# 02_-_MCU.net
KiCad netlist of a schematic drawn in Altium Designer
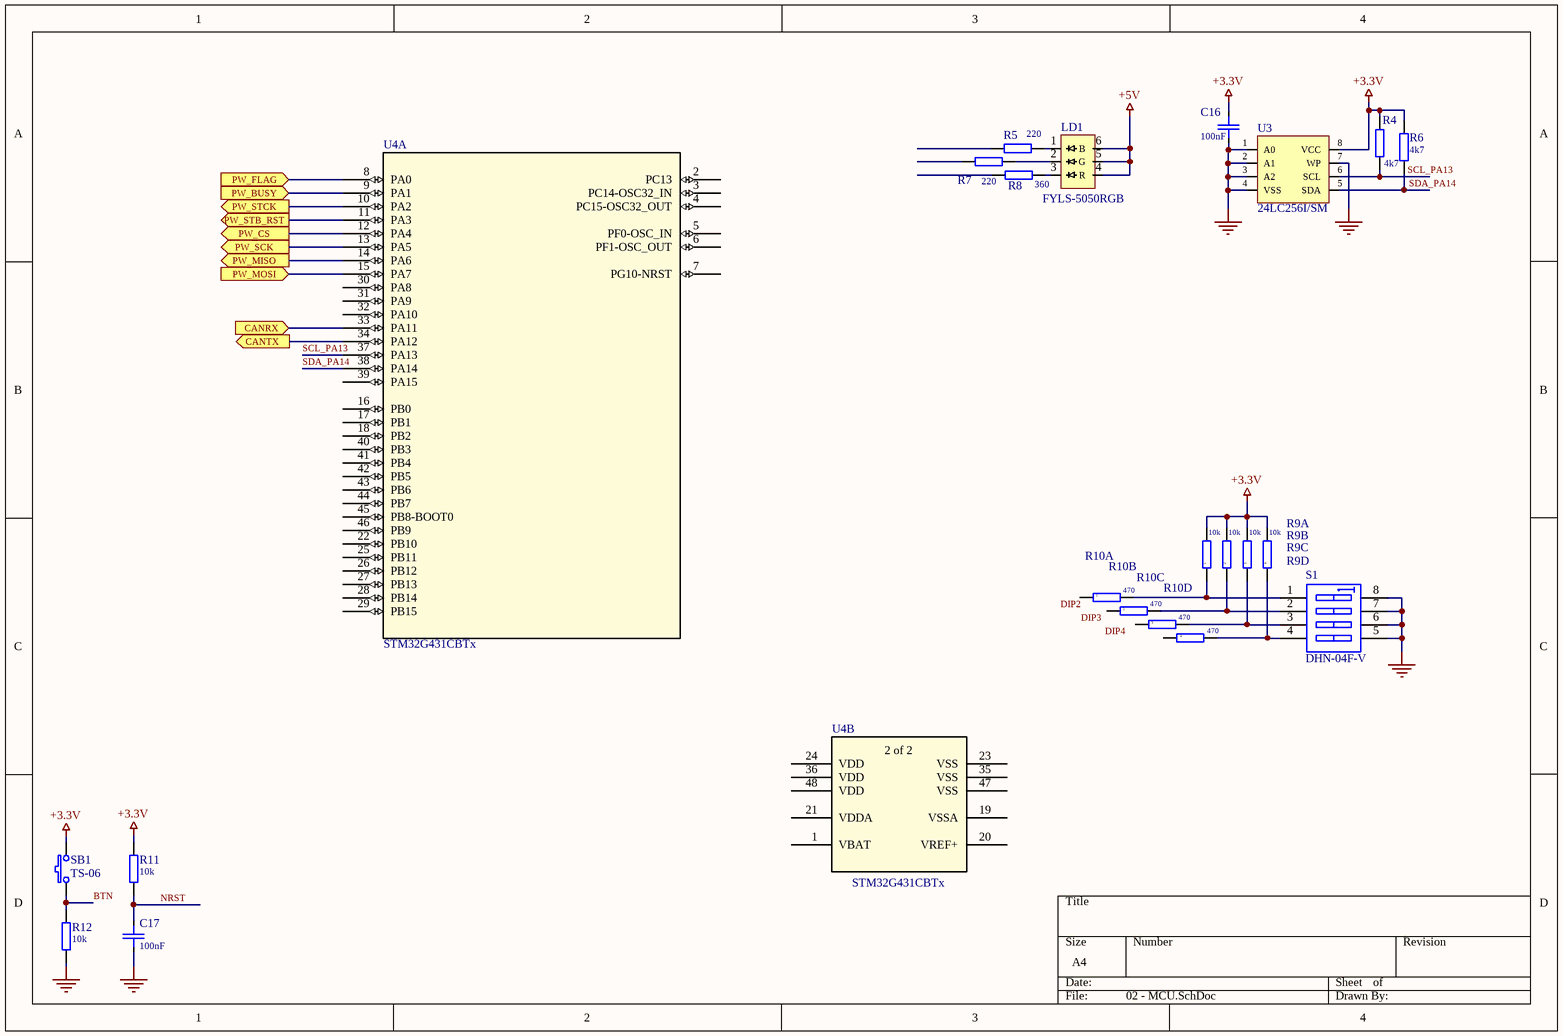
[diagram p0: 02 - MCU.SchDoc]

(export (version "E")
  (design (tool "Eeschema 10.0.6"))
  (components
    (comp (ref "C16")
      (value "100nF")
      (footprint "CAP: 0805")
      (description "SMD-0805")
      (libsource (lib "RCL_SMD_Integrated_Library1") (part "C-0805"))
    )
    (comp (ref "C17")
      (value "100nF")
      (footprint "CAP: 0805")
      (description "SMD-0805")
      (libsource (lib "RCL_SMD_Integrated_Library1") (part "C-0805"))
    )
    (comp (ref "LD1")
      (value "FYLS-5050RGB")
      (footprint "FYLS-5050RGB")
      (libsource (lib "stm32_Integrated_Library") (part "FYLS-5050RGB"))
    )
    (comp (ref "R4")
      (value "4k7")
      (footprint "RES: 0603")
      (description "SMD 0603 0.0625W 5% 50V")
      (libsource (lib "RCL_SMD_Integrated_Library") (part "R-0603"))
    )
    (comp (ref "R5")
      (value "220")
      (footprint "RES: 0603")
      (description "SMD 0603 0.0625W 5% 50V")
      (libsource (lib "RCL_SMD_Integrated_Library") (part "R-0603"))
    )
    (comp (ref "R6")
      (value "4k7")
      (footprint "RES: 0603")
      (description "SMD 0603 0.0625W 5% 50V")
      (libsource (lib "RCL_SMD_Integrated_Library") (part "R-0603"))
    )
    (comp (ref "R7")
      (value "220")
      (footprint "RES: 0603")
      (description "SMD 0603 0.0625W 5% 50V")
      (libsource (lib "RCL_SMD_Integrated_Library") (part "R-0603"))
    )
    (comp (ref "R8")
      (value "360")
      (footprint "RES: 0603")
      (description "SMD 0603 0.0625W 5% 50V")
      (libsource (lib "RCL_SMD_Integrated_Library") (part "R-0603"))
    )
    (comp (ref "R9")
      (value "10k")
      (footprint "RM4x0603")
      (description "SMD 4RM-0603 1\\16W 5%")
      (libsource (lib "SMD-RCL") (part "4RM-0603"))
    )
    (comp (ref "R10")
      (value "470")
      (footprint "RM4x0603")
      (description "SMD 4RM-0603 1\\16W 5%")
      (libsource (lib "SMD-RCL") (part "4RM-0603"))
    )
    (comp (ref "R11")
      (value "10k")
      (footprint "RES: 0603")
      (description "SMD 0603 0.0625W 5% 50V")
      (libsource (lib "RCL_SMD_Integrated_Library") (part "R-0603"))
    )
    (comp (ref "R12")
      (value "10k")
      (footprint "RES: 0603")
      (description "SMD 0603 0.0625W 5% 50V")
      (libsource (lib "RCL_SMD_Integrated_Library1") (part "R-0603"))
    )
    (comp (ref "S1")
      (value "DHN-04F-V")
      (footprint "SOIC-8-DIP_W")
      (description "DIP Switch, 4 Position, SPST")
      (fields (field (name "PUBLISHER") "Altium Limited"))
      (libsource (lib "Miscellaneous Devices") (part "SW DIP-4"))
    )
    (comp (ref "SB1") (value "TS-06") (footprint "TS-06") (libsource (lib "Devise") (part "Buton TS-06")))
    (comp (ref "U3")
      (value "24LC256I/SM")
      (footprint "SOP-8N (SOIJ)")
      (libsource (lib "stm32_Integrated_Library") (part "24LC256I/SM"))
    )
    (comp (ref "U4")
      (value "STM32G431CBTx")
      (footprint "LQFP48-7x7mm")
      (fields
        (field (name "MANUFACTURER_PART_NUMBER") "stm32g4_lqfp48_t1")
        (field (name "COPYRIGHT") "Copyright (C) 2016 Accelerated Designs. All rights reserved")
      )
      (libsource (lib "ST Microelectronics STM32 G4") (part "STM32G431CBTx"))
    )
  )
  (nets
    (net (code "1") (name "+3.3V") (class "Default")
      (node (ref "C16") (pin "1") (pinfunction "1_1") (pintype "passive"))
      (node (ref "R11") (pin "1") (pinfunction "1_1") (pintype "passive"))
      (node (ref "R4") (pin "2") (pinfunction "2_2") (pintype "passive"))
      (node (ref "R6") (pin "2") (pinfunction "2_2") (pintype "passive"))
      (node (ref "R9") (pin "5") (pinfunction "5_5") (pintype "passive"))
      (node (ref "R9") (pin "6") (pinfunction "6_6") (pintype "passive"))
      (node (ref "R9") (pin "7") (pinfunction "7_7") (pintype "passive"))
      (node (ref "R9") (pin "8") (pinfunction "8_8") (pintype "passive"))
      (node (ref "SB1") (pin "2") (pinfunction "2_2") (pintype "passive"))
      (node (ref "U3") (pin "8") (pinfunction "VCC_8") (pintype "passive"))
    )
    (net (code "2") (name "+5V") (class "Default")
      (node (ref "LD1") (pin "4") (pinfunction "R_4") (pintype "passive"))
      (node (ref "LD1") (pin "5") (pinfunction "G_5") (pintype "passive"))
      (node (ref "LD1") (pin "6") (pinfunction "B_6") (pintype "passive"))
    )
    (net (code "3") (name "/BTN") (class "Default")
      (node (ref "R12") (pin "1") (pinfunction "1_1") (pintype "passive"))
      (node (ref "SB1") (pin "1") (pinfunction "1_1") (pintype "passive"))
    )
    (net (code "4") (name "/CANRX") (class "Default")
      (node (ref "U4") (pin "33") (pinfunction "PA11_33") (pintype "bidirectional"))
    )
    (net (code "5") (name "/CANTX") (class "Default")
      (node (ref "U4") (pin "34") (pinfunction "PA12_34") (pintype "bidirectional"))
    )
    (net (code "9") (name "/NRST") (class "Default")
      (node (ref "C17") (pin "1") (pinfunction "1_1") (pintype "passive"))
      (node (ref "R11") (pin "2") (pinfunction "2_2") (pintype "passive"))
    )
    (net (code "10") (name "/PW_BUSY") (class "Default")
      (node (ref "U4") (pin "9") (pinfunction "PA1_9") (pintype "bidirectional"))
    )
    (net (code "11") (name "/PW_CS") (class "Default")
      (node (ref "U4") (pin "12") (pinfunction "PA4_12") (pintype "bidirectional"))
    )
    (net (code "12") (name "/PW_FLAG") (class "Default")
      (node (ref "U4") (pin "8") (pinfunction "PA0_8") (pintype "bidirectional"))
    )
    (net (code "13") (name "/PW_MISO") (class "Default")
      (node (ref "U4") (pin "14") (pinfunction "PA6_14") (pintype "bidirectional"))
    )
    (net (code "14") (name "/PW_MOSI") (class "Default")
      (node (ref "U4") (pin "15") (pinfunction "PA7_15") (pintype "bidirectional"))
    )
    (net (code "15") (name "/PW_SCK") (class "Default")
      (node (ref "U4") (pin "13") (pinfunction "PA5_13") (pintype "bidirectional"))
    )
    (net (code "16") (name "/PW_STB_RST") (class "Default")
      (node (ref "U4") (pin "11") (pinfunction "PA3_11") (pintype "bidirectional"))
    )
    (net (code "17") (name "/PW_STCK") (class "Default")
      (node (ref "U4") (pin "10") (pinfunction "PA2_10") (pintype "bidirectional"))
    )
    (net (code "18") (name "/SCL_PA13") (class "Default")
      (node (ref "R4") (pin "1") (pinfunction "1_1") (pintype "passive"))
      (node (ref "U3") (pin "6") (pinfunction "SCL_6") (pintype "passive"))
      (node (ref "U4") (pin "37") (pinfunction "PA13_37") (pintype "bidirectional"))
    )
    (net (code "19") (name "/SDA_PA14") (class "Default")
      (node (ref "R6") (pin "1") (pinfunction "1_1") (pintype "passive"))
      (node (ref "U3") (pin "5") (pinfunction "SDA_5") (pintype "passive"))
      (node (ref "U4") (pin "38") (pinfunction "PA14_38") (pintype "bidirectional"))
    )
    (net (code "20") (name "GND") (class "Default")
      (node (ref "C16") (pin "2") (pinfunction "2_2") (pintype "passive"))
      (node (ref "C17") (pin "2") (pinfunction "2_2") (pintype "passive"))
      (node (ref "R12") (pin "2") (pinfunction "2_2") (pintype "passive"))
      (node (ref "S1") (pin "5") (pinfunction "B4_5") (pintype "passive"))
      (node (ref "S1") (pin "6") (pinfunction "B3_6") (pintype "passive"))
      (node (ref "S1") (pin "7") (pinfunction "B2_7") (pintype "passive"))
      (node (ref "S1") (pin "8") (pinfunction "B1_8") (pintype "passive"))
      (node (ref "U3") (pin "1") (pinfunction "A0_1") (pintype "passive"))
      (node (ref "U3") (pin "2") (pinfunction "A1_2") (pintype "passive"))
      (node (ref "U3") (pin "3") (pinfunction "A2_3") (pintype "passive"))
      (node (ref "U3") (pin "4") (pinfunction "VSS_4") (pintype "passive"))
      (node (ref "U3") (pin "7") (pinfunction "WP_7") (pintype "passive"))
    )
    (net (code "21") (name "Net-(LD1-Pad1)") (class "Default")
      (node (ref "LD1") (pin "1") (pintype "passive"))
      (node (ref "R5") (pin "2") (pinfunction "2_2") (pintype "passive"))
    )
    (net (code "22") (name "Net-(LD1-Pad2)") (class "Default")
      (node (ref "LD1") (pin "2") (pintype "passive"))
      (node (ref "R7") (pin "2") (pinfunction "2_2") (pintype "passive"))
    )
    (net (code "23") (name "Net-(LD1-Pad3)") (class "Default")
      (node (ref "LD1") (pin "3") (pintype "passive"))
      (node (ref "R8") (pin "2") (pinfunction "2_2") (pintype "passive"))
    )
    (net (code "24") (name "Net-(S1-A1)") (class "Default")
      (node (ref "R10") (pin "8") (pinfunction "8_8") (pintype "passive"))
      (node (ref "R9") (pin "1") (pinfunction "1_1") (pintype "passive"))
      (node (ref "S1") (pin "1") (pinfunction "A1_1") (pintype "passive"))
    )
    (net (code "25") (name "Net-(S1-A2)") (class "Default")
      (node (ref "R10") (pin "7") (pinfunction "7_7") (pintype "passive"))
      (node (ref "R9") (pin "2") (pinfunction "2_2") (pintype "passive"))
      (node (ref "S1") (pin "2") (pinfunction "A2_2") (pintype "passive"))
    )
    (net (code "26") (name "Net-(S1-A3)") (class "Default")
      (node (ref "R10") (pin "6") (pinfunction "6_6") (pintype "passive"))
      (node (ref "R9") (pin "3") (pinfunction "3_3") (pintype "passive"))
      (node (ref "S1") (pin "3") (pinfunction "A3_3") (pintype "passive"))
    )
    (net (code "27") (name "Net-(S1-A4)") (class "Default")
      (node (ref "R10") (pin "5") (pinfunction "5_5") (pintype "passive"))
      (node (ref "R9") (pin "4") (pinfunction "4_4") (pintype "passive"))
      (node (ref "S1") (pin "4") (pinfunction "A4_4") (pintype "passive"))
    )
    (net (code "28") (name "unconnected-(R5-Pad1)") (class "Default")
      (node (ref "R5") (pin "1") (pinfunction "1_1") (pintype "passive"))
    )
    (net (code "29") (name "unconnected-(R7-Pad1)") (class "Default")
      (node (ref "R7") (pin "1") (pinfunction "1_1") (pintype "passive"))
    )
    (net (code "30") (name "unconnected-(R8-Pad1)") (class "Default")
      (node (ref "R8") (pin "1") (pinfunction "1_1") (pintype "passive"))
    )
    (net (code "31") (name "unconnected-(R10-Pad1)") (class "Default")
      (node (ref "R10") (pin "1") (pinfunction "1_1") (pintype "passive"))
    )
    (net (code "32") (name "unconnected-(R10-Pad2)") (class "Default")
      (node (ref "R10") (pin "2") (pinfunction "2_2") (pintype "passive"))
    )
    (net (code "33") (name "unconnected-(R10-Pad3)") (class "Default")
      (node (ref "R10") (pin "3") (pinfunction "3_3") (pintype "passive"))
    )
    (net (code "34") (name "unconnected-(R10-Pad4)") (class "Default")
      (node (ref "R10") (pin "4") (pinfunction "4_4") (pintype "passive"))
    )
    (net (code "35") (name "unconnected-(U4A-PA8-Pad30)") (class "Default")
      (node (ref "U4") (pin "30") (pinfunction "PA8_30") (pintype "bidirectional"))
    )
    (net (code "36") (name "unconnected-(U4A-PA9-Pad31)") (class "Default")
      (node (ref "U4") (pin "31") (pinfunction "PA9_31") (pintype "bidirectional"))
    )
    (net (code "37") (name "unconnected-(U4A-PA10-Pad32)") (class "Default")
      (node (ref "U4") (pin "32") (pinfunction "PA10_32") (pintype "bidirectional"))
    )
    (net (code "38") (name "unconnected-(U4A-PA15-Pad39)") (class "Default")
      (node (ref "U4") (pin "39") (pinfunction "PA15_39") (pintype "bidirectional"))
    )
    (net (code "39") (name "unconnected-(U4A-PB0-Pad16)") (class "Default")
      (node (ref "U4") (pin "16") (pinfunction "PB0_16") (pintype "bidirectional"))
    )
    (net (code "40") (name "unconnected-(U4A-PB1-Pad17)") (class "Default")
      (node (ref "U4") (pin "17") (pinfunction "PB1_17") (pintype "bidirectional"))
    )
    (net (code "41") (name "unconnected-(U4A-PB2-Pad18)") (class "Default")
      (node (ref "U4") (pin "18") (pinfunction "PB2_18") (pintype "bidirectional"))
    )
    (net (code "42") (name "unconnected-(U4A-PB3-Pad40)") (class "Default")
      (node (ref "U4") (pin "40") (pinfunction "PB3_40") (pintype "bidirectional"))
    )
    (net (code "43") (name "unconnected-(U4A-PB4-Pad41)") (class "Default")
      (node (ref "U4") (pin "41") (pinfunction "PB4_41") (pintype "bidirectional"))
    )
    (net (code "44") (name "unconnected-(U4A-PB5-Pad42)") (class "Default")
      (node (ref "U4") (pin "42") (pinfunction "PB5_42") (pintype "bidirectional"))
    )
    (net (code "45") (name "unconnected-(U4A-PB6-Pad43)") (class "Default")
      (node (ref "U4") (pin "43") (pinfunction "PB6_43") (pintype "bidirectional"))
    )
    (net (code "46") (name "unconnected-(U4A-PB7-Pad44)") (class "Default")
      (node (ref "U4") (pin "44") (pinfunction "PB7_44") (pintype "bidirectional"))
    )
    (net (code "47") (name "unconnected-(U4A-PB8-BOOT0-Pad45)") (class "Default")
      (node (ref "U4") (pin "45") (pinfunction "PB8-BOOT0_45") (pintype "bidirectional"))
    )
    (net (code "48") (name "unconnected-(U4A-PB9-Pad46)") (class "Default")
      (node (ref "U4") (pin "46") (pinfunction "PB9_46") (pintype "bidirectional"))
    )
    (net (code "49") (name "unconnected-(U4A-PB10-Pad22)") (class "Default")
      (node (ref "U4") (pin "22") (pinfunction "PB10_22") (pintype "bidirectional"))
    )
    (net (code "50") (name "unconnected-(U4A-PB11-Pad25)") (class "Default")
      (node (ref "U4") (pin "25") (pinfunction "PB11_25") (pintype "bidirectional"))
    )
    (net (code "51") (name "unconnected-(U4A-PB12-Pad26)") (class "Default")
      (node (ref "U4") (pin "26") (pinfunction "PB12_26") (pintype "bidirectional"))
    )
    (net (code "52") (name "unconnected-(U4A-PB13-Pad27)") (class "Default")
      (node (ref "U4") (pin "27") (pinfunction "PB13_27") (pintype "bidirectional"))
    )
    (net (code "53") (name "unconnected-(U4A-PB14-Pad28)") (class "Default")
      (node (ref "U4") (pin "28") (pinfunction "PB14_28") (pintype "bidirectional"))
    )
    (net (code "54") (name "unconnected-(U4A-PB15-Pad29)") (class "Default")
      (node (ref "U4") (pin "29") (pinfunction "PB15_29") (pintype "bidirectional"))
    )
    (net (code "55") (name "unconnected-(U4A-PC13-Pad2)") (class "Default")
      (node (ref "U4") (pin "2") (pinfunction "PC13_2") (pintype "bidirectional"))
    )
    (net (code "56") (name "unconnected-(U4A-PC14-OSC32_IN-Pad3)") (class "Default")
      (node (ref "U4") (pin "3") (pinfunction "PC14-OSC32_IN_3") (pintype "bidirectional"))
    )
    (net (code "57") (name "unconnected-(U4A-PC15-OSC32_OUT-Pad4)") (class "Default")
      (node (ref "U4") (pin "4") (pinfunction "PC15-OSC32_OUT_4") (pintype "bidirectional"))
    )
    (net (code "58") (name "unconnected-(U4A-PF0-OSC_IN-Pad5)") (class "Default")
      (node (ref "U4") (pin "5") (pinfunction "PF0-OSC_IN_5") (pintype "bidirectional"))
    )
    (net (code "59") (name "unconnected-(U4A-PF1-OSC_OUT-Pad6)") (class "Default")
      (node (ref "U4") (pin "6") (pinfunction "PF1-OSC_OUT_6") (pintype "bidirectional"))
    )
    (net (code "60") (name "unconnected-(U4A-PG10-NRST-Pad7)") (class "Default")
      (node (ref "U4") (pin "7") (pinfunction "PG10-NRST_7") (pintype "bidirectional"))
    )
    (net (code "61") (name "unconnected-(U4B-VBAT-Pad1)") (class "Default")
      (node (ref "U4") (pin "1") (pinfunction "VBAT_1") (pintype "power_in"))
    )
    (net (code "62") (name "unconnected-(U4B-VDD-Pad24)") (class "Default")
      (node (ref "U4") (pin "24") (pinfunction "VDD_24") (pintype "power_in"))
    )
    (net (code "63") (name "unconnected-(U4B-VDD-Pad36)") (class "Default")
      (node (ref "U4") (pin "36") (pinfunction "VDD_36") (pintype "power_in"))
    )
    (net (code "64") (name "unconnected-(U4B-VDD-Pad48)") (class "Default")
      (node (ref "U4") (pin "48") (pinfunction "VDD_48") (pintype "power_in"))
    )
    (net (code "65") (name "unconnected-(U4B-VDDA-Pad21)") (class "Default")
      (node (ref "U4") (pin "21") (pinfunction "VDDA_21") (pintype "power_in"))
    )
    (net (code "66") (name "unconnected-(U4B-VREF+-Pad20)") (class "Default")
      (node (ref "U4") (pin "20") (pinfunction "VREF+_20") (pintype "power_in"))
    )
    (net (code "67") (name "unconnected-(U4B-VSS-Pad23)") (class "Default")
      (node (ref "U4") (pin "23") (pinfunction "VSS_23") (pintype "power_in"))
    )
    (net (code "68") (name "unconnected-(U4B-VSS-Pad35)") (class "Default")
      (node (ref "U4") (pin "35") (pinfunction "VSS_35") (pintype "power_in"))
    )
    (net (code "69") (name "unconnected-(U4B-VSS-Pad47)") (class "Default")
      (node (ref "U4") (pin "47") (pinfunction "VSS_47") (pintype "power_in"))
    )
    (net (code "70") (name "unconnected-(U4B-VSSA-Pad19)") (class "Default")
      (node (ref "U4") (pin "19") (pinfunction "VSSA_19") (pintype "power_in"))
    )
  )
)
